# PoE.net
KiCad netlist of a schematic drawn in Altium Designer
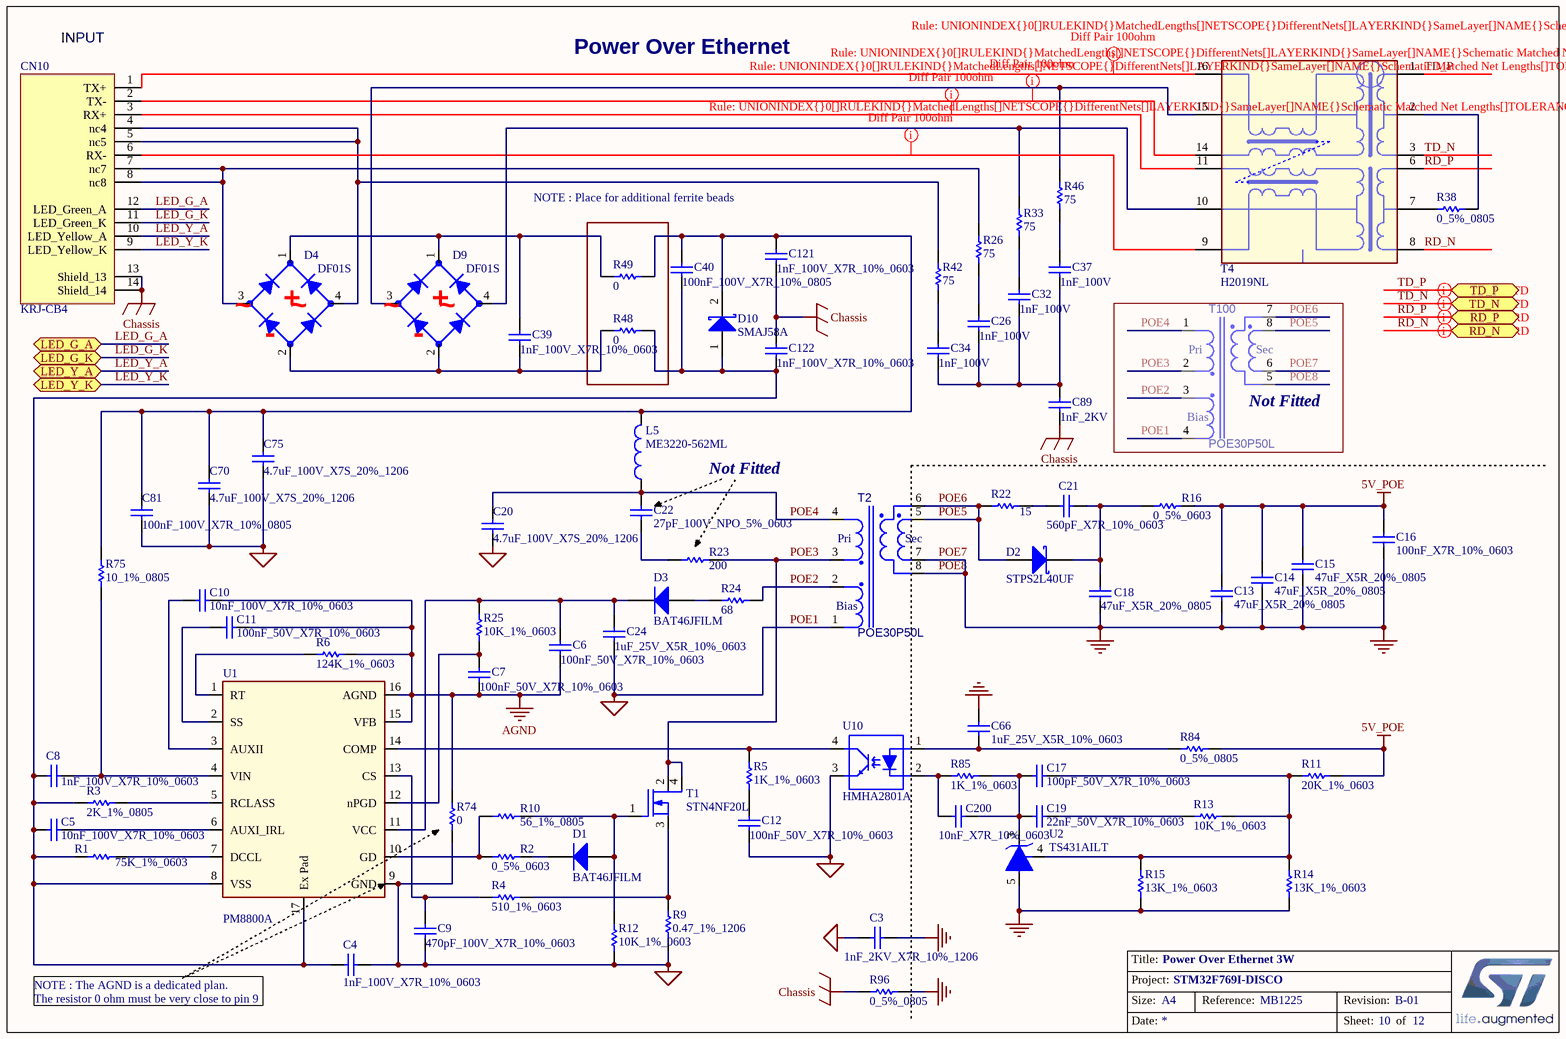
[diagram p0: PoE.SchDoc]

(export (version "E")
  (design (tool "Eeschema 10.0.6"))
  (components
    (comp (ref "C3")
      (value "1nF_2KV_X7R_10%_1206")
      (footprint "1206C")
      (description "Capacitor,1nF,2KV,X7R,10%,1206,YAGEO")
      (libsource (lib "MCD_TOOLS_CAPACITOR") (part "Cap_1nF_2KV_X7R_10%_1206"))
    )
    (comp (ref "C4")
      (value "1nF_100V_X7R_10%_0603")
      (footprint "0603C")
      (description "Capacitor,1nF,100V,X7R,10%,0603,YAGEO")
      (libsource (lib "MCD_TOOLS_CAPACITOR") (part "Cap_1nF_100V_X7R_10%_0603"))
    )
    (comp (ref "C5")
      (value "10nF_100V_X7R_10%_0603")
      (footprint "0603C")
      (description "Capacitor,10nF,100V,X7R,10%,0603,YAGEO")
      (libsource (lib "MCD_TOOLS_CAPACITOR") (part "Cap_10nF_100V_X7R_10%_0603"))
    )
    (comp (ref "C6")
      (value "100nF_50V_X7R_10%_0603")
      (footprint "0603C")
      (description "Capacitor,100nF,50V,X7R,10%,0603,YAGEO")
      (libsource (lib "MCD_TOOLS_CAPACITOR") (part "Cap_100nF_50V_X7R_10%_0603"))
    )
    (comp (ref "C7")
      (value "100nF_50V_X7R_10%_0603")
      (footprint "0603C")
      (description "Capacitor,100nF,50V,X7R,10%,0603,YAGEO")
      (libsource (lib "MCD_TOOLS_CAPACITOR") (part "Cap_100nF_50V_X7R_10%_0603"))
    )
    (comp (ref "C8")
      (value "1nF_100V_X7R_10%_0603")
      (footprint "0603C")
      (description "Capacitor,1nF,100V,X7R,10%,0603,YAGEO")
      (libsource (lib "MCD_TOOLS_CAPACITOR") (part "Cap_1nF_100V_X7R_10%_0603"))
    )
    (comp (ref "C9")
      (value "470pF_100V_X7R_10%_0603")
      (footprint "0603C")
      (description "Capacitor,470pF,100V,X7R,10%,0603,AVX")
      (libsource (lib "MCD_TOOLS_CAPACITOR") (part "Cap_470pF_100V_X7R_10%_0603"))
    )
    (comp (ref "C10")
      (value "10nF_100V_X7R_10%_0603")
      (footprint "0603C")
      (description "Capacitor,10nF,100V,X7R,10%,0603,YAGEO")
      (libsource (lib "MCD_TOOLS_CAPACITOR") (part "Cap_10nF_100V_X7R_10%_0603"))
    )
    (comp (ref "C11")
      (value "100nF_50V_X7R_10%_0603")
      (footprint "0603C")
      (description "Capacitor,100nF,50V,X7R,10%,0603,YAGEO")
      (libsource (lib "MCD_TOOLS_CAPACITOR") (part "Cap_100nF_50V_X7R_10%_0603"))
    )
    (comp (ref "C12")
      (value "100nF_50V_X7R_10%_0603")
      (footprint "0603C")
      (description "Capacitor,100nF,50V,X7R,10%,0603,YAGEO")
      (libsource (lib "MCD_TOOLS_CAPACITOR") (part "Cap_100nF_50V_X7R_10%_0603"))
    )
    (comp (ref "C13")
      (value "47uF_X5R_20%_0805")
      (footprint "0805C")
      (description "Capacitor,47uF,10V,X5R,20%,0805,MURATA")
      (libsource (lib "MCD_TOOLS_CAPACITOR") (part "Cap_47uF_X5R_20%_0805"))
    )
    (comp (ref "C14")
      (value "47uF_X5R_20%_0805")
      (footprint "0805C")
      (description "Capacitor,47uF,10V,X5R,20%,0805,MURATA")
      (libsource (lib "MCD_TOOLS_CAPACITOR") (part "Cap_47uF_X5R_20%_0805"))
    )
    (comp (ref "C15")
      (value "47uF_X5R_20%_0805")
      (footprint "0805C")
      (description "Capacitor,47uF,10V,X5R,20%,0805,MURATA")
      (libsource (lib "MCD_TOOLS_CAPACITOR") (part "Cap_47uF_X5R_20%_0805"))
    )
    (comp (ref "C16")
      (value "100nF_X7R_10%_0603")
      (footprint "0603C")
      (description "Capacitor,100nF,16V,X7R,10%,0603,YAGEO")
      (libsource (lib "MCD_TOOLS_CAPACITOR") (part "Cap_100nF_X7R_10%_0603"))
    )
    (comp (ref "C17")
      (value "100pF_50V_X7R_10%_0603")
      (footprint "0603C")
      (description "Capacitor,100pF,50V,X7R,10%,0603,AVX")
      (libsource (lib "MCD_TOOLS_CAPACITOR") (part "Cap_100pF_50V_X7R_10%_0603"))
    )
    (comp (ref "C18")
      (value "47uF_X5R_20%_0805")
      (footprint "0805C")
      (description "Capacitor,47uF,10V,X5R,20%,0805,MURATA")
      (libsource (lib "MCD_TOOLS_CAPACITOR") (part "Cap_47uF_X5R_20%_0805"))
    )
    (comp (ref "C19")
      (value "22nF_50V_X7R_10%_0603")
      (footprint "0603C")
      (description "Capacitor,22nF,50V,X7R,10%,0603,YAGEO")
      (libsource (lib "MCD_TOOLS_CAPACITOR") (part "Cap_22nF_50V_X7R_10%_0603"))
    )
    (comp (ref "C20")
      (value "4.7uF_100V_X7S_20%_1206")
      (footprint "1206C")
      (description "Capacitor,4.7uF,100V, X7S,20%,1206,AVX")
      (libsource (lib "MCD_TOOLS_CAPACITOR") (part "Cap_4.7uF_100V_X7S_20%_1206"))
    )
    (comp (ref "C21")
      (value "560pF_X7R_10%_0603")
      (footprint "0603C")
      (description "Capacitor,560pF,16V,X7R,10%,0603,AVX")
      (libsource (lib "MCD_TOOLS_CAPACITOR") (part "Cap_560pF_X7R_10%_0603"))
    )
    (comp (ref "C22")
      (value "27pF_100V_NPO_5%_0603")
      (footprint "0603C")
      (description "Capacitor,27pF,100V,NPO,5%,0603,YAGEO")
      (libsource (lib "MCD_TOOLS_CAPACITOR") (part "Cap_27pF_100V_NPO_5%_0603"))
    )
    (comp (ref "C24")
      (value "1uF_25V_X5R_10%_0603")
      (footprint "0603C")
      (description "Capacitor,1uF,25V,X5R,10%,0603,YAGEO")
      (libsource (lib "MCD_TOOLS_CAPACITOR") (part "Cap_1uF_25V_X5R_10%_0603"))
    )
    (comp (ref "C26")
      (value "1nF_100V")
      (footprint "0603C")
      (description "Capacitor,1nF,100V,X7R,10%,0603,YAGEO")
      (libsource (lib "MCD_TOOLS_CAPACITOR") (part "Cap_1nF_100V_X7R_10%_0603"))
    )
    (comp (ref "C32")
      (value "1nF_100V")
      (footprint "0603C")
      (description "Capacitor,1nF,100V,X7R,10%,0603,YAGEO")
      (libsource (lib "MCD_TOOLS_CAPACITOR") (part "Cap_1nF_100V_X7R_10%_0603"))
    )
    (comp (ref "C34")
      (value "1nF_100V")
      (footprint "0603C")
      (description "Capacitor,1nF,100V,X7R,10%,0603,YAGEO")
      (libsource (lib "MCD_TOOLS_CAPACITOR") (part "Cap_1nF_100V_X7R_10%_0603"))
    )
    (comp (ref "C37")
      (value "1nF_100V")
      (footprint "0603C")
      (description "Capacitor,1nF,100V,X7R,10%,0603,YAGEO")
      (libsource (lib "MCD_TOOLS_CAPACITOR") (part "Cap_1nF_100V_X7R_10%_0603"))
    )
    (comp (ref "C39")
      (value "1nF_100V_X7R_10%_0603")
      (footprint "0603C")
      (description "Capacitor,1nF,100V,X7R,10%,0603,YAGEO")
      (libsource (lib "MCD_TOOLS_CAPACITOR") (part "Cap_1nF_100V_X7R_10%_0603"))
    )
    (comp (ref "C40")
      (value "100nF_100V_X7R_10%_0805")
      (footprint "0805C")
      (description "Capacitor,100nF,100V,X7R,10%,0805,TDK")
      (libsource (lib "MCD_TOOLS_CAPACITOR") (part "Cap_100nF_100V_X7R_10%_0805"))
    )
    (comp (ref "C66")
      (value "1uF_25V_X5R_10%_0603")
      (footprint "0603C")
      (description "Capacitor,1uF,25V,X5R,10%,0603,YAGEO")
      (libsource (lib "MCD_TOOLS_CAPACITOR") (part "Cap_1uF_25V_X5R_10%_0603"))
    )
    (comp (ref "C70")
      (value "4.7uF_100V_X7S_20%_1206")
      (footprint "1206C")
      (description "Capacitor,4.7uF,100V, X7S,20%,1206,AVX")
      (libsource (lib "MCD_TOOLS_CAPACITOR") (part "Cap_4.7uF_100V_X7S_20%_1206"))
    )
    (comp (ref "C75")
      (value "4.7uF_100V_X7S_20%_1206")
      (footprint "1206C")
      (description "Capacitor,4.7uF,100V, X7S,20%,1206,AVX")
      (libsource (lib "MCD_TOOLS_CAPACITOR") (part "Cap_4.7uF_100V_X7S_20%_1206"))
    )
    (comp (ref "C81")
      (value "100nF_100V_X7R_10%_0805")
      (footprint "0805C")
      (description "Capacitor,100nF,100V,X7R,10%,0805,TDK")
      (libsource (lib "MCD_TOOLS_CAPACITOR") (part "Cap_100nF_100V_X7R_10%_0805"))
    )
    (comp (ref "C89")
      (value "1nF_2KV")
      (footprint "1206C")
      (description "Capacitor,1nF,2KV,X7R,10%,1206,YAGEO")
      (libsource (lib "MCD_TOOLS_CAPACITOR") (part "Cap_1nF_2KV_X7R_10%_1206"))
    )
    (comp (ref "C121")
      (value "1nF_100V_X7R_10%_0603")
      (footprint "0603C")
      (description "Capacitor,1nF,100V,X7R,10%,0603,YAGEO")
      (libsource (lib "MCD_TOOLS_CAPACITOR") (part "Cap_1nF_100V_X7R_10%_0603"))
    )
    (comp (ref "C122")
      (value "1nF_100V_X7R_10%_0603")
      (footprint "0603C")
      (description "Capacitor,1nF,100V,X7R,10%,0603,YAGEO")
      (libsource (lib "MCD_TOOLS_CAPACITOR") (part "Cap_1nF_100V_X7R_10%_0603"))
    )
    (comp (ref "C200")
      (value "10nF_X7R_10%_0603")
      (footprint "0603C")
      (description "Capacitor,10nF,50V,X7R,10%,0603,YAGEO")
      (libsource (lib "MCD_TOOLS_CAPACITOR") (part "Cap_10nF_X7R_10%_0603"))
    )
    (comp (ref "CN10")
      (value "KRJ-CB4")
      (footprint "RJ45_LED_KRJ-CB4R2GYZNL_EM")
      (description "100 Base-TX (Fast Ethernet)  RJ45 single port (1x1) with LEDS Integrated Connector")
      (libsource (lib "MCD_TOOLS_CONNECTOR") (part "KRJ-CB4"))
    )
    (comp (ref "D1")
      (value "BAT46JFILM")
      (footprint "SOD-323")
      (description "Schottky Single diode(150mA, 100V)")
      (libsource (lib "MCD_TOOLS_MISCELLANEOUS") (part "BAT46JFILM"))
    )
    (comp (ref "D2")
      (value "STPS2L40UF")
      (footprint "SMB")
      (description "Low drop power Schottky rectifier(2A, 40V, 0.34V)")
      (libsource (lib "MCD_TOOLS_MISCELLANEOUS") (part "STPS2L40UF"))
    )
    (comp (ref "D3")
      (value "BAT46JFILM")
      (footprint "SOD-323")
      (description "Schottky Single diode(150mA, 100V)")
      (libsource (lib "MCD_TOOLS_MISCELLANEOUS") (part "BAT46JFILM"))
    )
    (comp (ref "D4")
      (value "DF01S")
      (footprint "DBS101-107G")
      (description "Surface Mount Bridge Rectifiers")
      (libsource (lib "MCD_TOOLS_MISCELLANEOUS") (part "DF01S_SMD"))
    )
    (comp (ref "D9")
      (value "DF01S")
      (footprint "DBS101-107G")
      (description "Surface Mount Bridge Rectifiers")
      (libsource (lib "MCD_TOOLS_MISCELLANEOUS") (part "DF01S_SMD"))
    )
    (comp (ref "D10")
      (value "SMAJ58A")
      (footprint "SMA")
      (description "Transil 400W, VRM=58V")
      (libsource (lib "MCD_TOOLS_MISCELLANEOUS") (part "SMAJ58A"))
    )
    (comp (ref "L5")
      (value "ME3220-562ML")
      (footprint "LSM2_3R2X2R8_H2")
      (description "Power Inductor, 5.6uH, 0.2R, ME3220-562ML, CoilCraft")
      (libsource (lib "MCD_TOOLS_MISCELLANEOUS") (part "ME3220-562ML"))
    )
    (comp (ref "R1")
      (value "75K_1%_0603")
      (footprint "0603R")
      (description "Resistor,75K,0603,1%,YAGEO")
      (libsource (lib "MCD_TOOLS_RESISTOR") (part "Res_75K_1%_0603"))
    )
    (comp (ref "R2")
      (value "0_5%_0603")
      (footprint "0603R-GS")
      (description "Resistor,0,0603,5%,YAGEO")
      (libsource (lib "MCD_TOOLS_RESISTOR") (part "Res_0_5%_0603"))
    )
    (comp (ref "R3")
      (value "2K_1%_0805")
      (footprint "0805R")
      (description "Resistor,2K,0805,1%,YAGEO")
      (libsource (lib "MCD_TOOLS_RESISTOR") (part "Res_2K_1%_0805"))
    )
    (comp (ref "R4")
      (value "510_1%_0603")
      (footprint "0603R")
      (description "Resistor,510,0603,1%,YAGEO")
      (libsource (lib "MCD_TOOLS_RESISTOR") (part "Res_510_1%_0603"))
    )
    (comp (ref "R5")
      (value "1K_1%_0603")
      (footprint "0603R")
      (description "Resistor,1K,0603,1%,YAGEO")
      (libsource (lib "MCD_TOOLS_RESISTOR") (part "Res_1K_1%_0603"))
    )
    (comp (ref "R6")
      (value "124K_1%_0603")
      (footprint "0603R")
      (description "Resistor,124K,0603,1%,YAGEO")
      (libsource (lib "MCD_TOOLS_RESISTOR") (part "Res_124K_1%_0603"))
    )
    (comp (ref "R9")
      (value "0.47_1%_1206")
      (footprint "1206R")
      (description "Resistor,0.47,1206,1%,YAGEO")
      (libsource (lib "MCD_TOOLS_RESISTOR") (part "Res_0.47_1%_1206"))
    )
    (comp (ref "R10")
      (value "56_1%_0805")
      (footprint "0805R")
      (description "Resistor,56,0805,1%,YAGEO")
      (libsource (lib "MCD_TOOLS_RESISTOR") (part "Res_56_1%_0805"))
    )
    (comp (ref "R11")
      (value "20K_1%_0603")
      (footprint "0603R")
      (description "Resistor,20K,0603,1%,YAGEO")
      (libsource (lib "MCD_TOOLS_RESISTOR") (part "Res_20K_1%_0603"))
    )
    (comp (ref "R12")
      (value "10K_1%_0603")
      (footprint "0603R")
      (description "Resistor,10K,0603,1%,YAGEO")
      (libsource (lib "MCD_TOOLS_RESISTOR") (part "Res_10K_1%_0603"))
    )
    (comp (ref "R13")
      (value "10K_1%_0603")
      (footprint "0603R")
      (description "Resistor,10K,0603,1%,YAGEO")
      (libsource (lib "MCD_TOOLS_RESISTOR") (part "Res_10K_1%_0603"))
    )
    (comp (ref "R14")
      (value "13K_1%_0603")
      (footprint "0603R")
      (description "Resistor,13K,0603,1%,YAGEO")
      (libsource (lib "MCD_TOOLS_RESISTOR") (part "Res_13K_1%_0603"))
    )
    (comp (ref "R15")
      (value "13K_1%_0603")
      (footprint "0603R")
      (description "Resistor,13K,0603,1%,YAGEO")
      (libsource (lib "MCD_TOOLS_RESISTOR") (part "Res_13K_1%_0603"))
    )
    (comp (ref "R16")
      (value "0_5%_0603")
      (footprint "0603R-GS")
      (description "Resistor,0,0603,5%,YAGEO")
      (libsource (lib "MCD_TOOLS_RESISTOR") (part "Res_0_5%_0603"))
    )
    (comp (ref "R22")
      (value "15")
      (footprint "0805R")
      (description "Resistor,15,0805,1%,YAGEO")
      (libsource (lib "MCD_TOOLS_RESISTOR") (part "Res_15_1%_0805"))
    )
    (comp (ref "R23")
      (value "200")
      (footprint "1206R")
      (description "Resistor,200,1206,1%,Rohm")
      (libsource (lib "MCD_TOOLS_RESISTOR") (part "Res_200_1%_1206"))
    )
    (comp (ref "R24")
      (value "68")
      (footprint "0805R")
      (description "Resistor,68,0805,1%,YAGEO")
      (libsource (lib "MCD_TOOLS_RESISTOR") (part "Res_68_1%_0805"))
    )
    (comp (ref "R25")
      (value "10K_1%_0603")
      (footprint "0603R")
      (description "Resistor,10K,0603,1%,YAGEO")
      (libsource (lib "MCD_TOOLS_RESISTOR") (part "Res_10K_1%_0603"))
    )
    (comp (ref "R26")
      (value "75")
      (footprint "0805R")
      (description "Resistor,75,0805,1%,YAGEO")
      (libsource (lib "MCD_TOOLS_RESISTOR") (part "Res_75_1%_0805"))
    )
    (comp (ref "R33")
      (value "75")
      (footprint "0805R")
      (description "Resistor,75,0805,1%,YAGEO")
      (libsource (lib "MCD_TOOLS_RESISTOR") (part "Res_75_1%_0805"))
    )
    (comp (ref "R38")
      (value "0_5%_0805")
      (footprint "0805R")
      (description "Resistor,0,0805,5%,YAGEO")
      (libsource (lib "MCD_TOOLS_RESISTOR") (part "Res_0_5%_0805"))
    )
    (comp (ref "R42")
      (value "75")
      (footprint "0805R")
      (description "Resistor,75,0805,1%,YAGEO")
      (libsource (lib "MCD_TOOLS_RESISTOR") (part "Res_75_1%_0805"))
    )
    (comp (ref "R46")
      (value "75")
      (footprint "0805R")
      (description "Resistor,75,0805,1%,YAGEO")
      (libsource (lib "MCD_TOOLS_RESISTOR") (part "Res_75_1%_0805"))
    )
    (comp (ref "R48")
      (value "0")
      (footprint "0805R")
      (description "Resistor,0,0805,5%,YAGEO")
      (libsource (lib "MCD_TOOLS_RESISTOR") (part "Res_0_5%_0805"))
    )
    (comp (ref "R49")
      (value "0")
      (footprint "0805R")
      (description "Resistor,0,0805,5%,YAGEO")
      (libsource (lib "MCD_TOOLS_RESISTOR") (part "Res_0_5%_0805"))
    )
    (comp (ref "R74")
      (value "0")
      (footprint "0603R-GS")
      (description "Resistor,0,0603,5%,YAGEO")
      (libsource (lib "MCD_TOOLS_RESISTOR") (part "Res_0_5%_0603"))
    )
    (comp (ref "R75")
      (value "10_1%_0805")
      (footprint "0805R")
      (description "Resistor,10,0805,1%,Stackpole,1/4W")
      (libsource (lib "MCD_TOOLS_RESISTOR") (part "Res_10_1%_0805"))
    )
    (comp (ref "R84")
      (value "0_5%_0805")
      (footprint "0805R")
      (description "Resistor,0,0805,5%,YAGEO")
      (libsource (lib "MCD_TOOLS_RESISTOR") (part "Res_0_5%_0805"))
    )
    (comp (ref "R85")
      (value "1K_1%_0603")
      (footprint "0603R")
      (description "Resistor,1K,0603,1%,YAGEO")
      (libsource (lib "MCD_TOOLS_RESISTOR") (part "Res_1K_1%_0603"))
    )
    (comp (ref "R96")
      (value "0_5%_0805")
      (footprint "0805R")
      (description "Resistor,0,0805,5%,YAGEO")
      (libsource (lib "MCD_TOOLS_RESISTOR") (part "Res_0_5%_0805"))
    )
    (comp (ref "T1")
      (value "STN4NF20L")
      (footprint "SOT-223")
      (description "N-channel 200 V, 1.1ohm, 1 A, low gate charge STripFET II, Power MOSFET")
      (libsource (lib "MCD_TOOLS_MISCELLANEOUS") (part "STN4NF20L"))
    )
    (comp (ref "T2")
      (value "POE30P50L")
      (footprint "TF_10R9X13R2-12R2X14R4_CPT")
      (description "Flyback Transformers for 3 Watt, PoE applications, CoilCraft Cyntec")
      (fields (field (name "PROVIDED") "Sub Co"))
      (libsource (lib "MCD_TOOLS_MISCELLANEOUS") (part "POE30P_C"))
    )
    (comp (ref "T4")
      (value "H2019NL")
      (footprint "TF_16SM_12R7X9R65")
      (description "10/100BASE-TX VoIP Magnetics Modules, Data Transformer")
      (libsource (lib "MCD_TOOLS_MISCELLANEOUS") (part "H2019"))
    )
    (comp (ref "T100")
      (value "POE30P50L")
      (footprint "TF_8SM_12R04X12R85")
      (description "Flyback Transformers for 3 Watt, PoE applications, Wurth")
      (fields (field (name "PROVIDED") "Sub Co"))
      (libsource (lib "MCD_TOOLS_MISCELLANEOUS") (part "POE30P_W"))
    )
    (comp (ref "U1")
      (value "PM8800A")
      (footprint "TSSOP16_0R65_5x6R4_TP")
      (fields (field (name "PROVIDED") "STM"))
      (libsource (lib "MCD_TOOLS_MISCELLANEOUS") (part "PM8800A"))
    )
    (comp (ref "U2")
      (value "TS431AILT")
      (footprint "SOT23-5")
      (description "Low voltage adjustable shunt reference")
      (libsource (lib "MCD_TOOLS_MISCELLANEOUS") (part "TS431AILT"))
    )
    (comp (ref "U10")
      (value "HMHA2801A")
      (footprint "PC_4SM_1R27_2R5X6R8")
      (description "OPTOISOLATOR 3.7KV TRANSISTOR 4SMD")
      (libsource (lib "MCD_TOOLS_MISCELLANEOUS") (part "HMHA2801A"))
    )
  )
  (nets
    (net (code "1") (name "/LED_G_A") (class "Default")
      (node (ref "CN10") (pin "12") (pinfunction "LED_Green_A_12") (pintype "passive"))
    )
    (net (code "2") (name "/LED_G_K") (class "Default")
      (node (ref "CN10") (pin "11") (pinfunction "LED_Green_K_11") (pintype "passive"))
    )
    (net (code "3") (name "/LED_Y_A") (class "Default")
      (node (ref "CN10") (pin "10") (pinfunction "LED_Yellow_A_10") (pintype "passive"))
    )
    (net (code "4") (name "/LED_Y_K") (class "Default")
      (node (ref "CN10") (pin "9") (pinfunction "LED_Yellow_K_9") (pintype "passive"))
    )
    (net (code "5") (name "/POE2") (class "Default")
      (node (ref "R24") (pin "2") (pinfunction "2_2") (pintype "passive"))
      (node (ref "T100") (pin "3") (pinfunction "3_3") (pintype "passive"))
      (node (ref "T2") (pin "2") (pinfunction "2_2") (pintype "passive"))
    )
    (net (code "6") (name "/POE3") (class "Default")
      (node (ref "R23") (pin "2") (pinfunction "2_2") (pintype "passive"))
      (node (ref "T1") (pin "2") (pinfunction "D_2") (pintype "passive"))
      (node (ref "T1") (pin "4") (pinfunction "D_4") (pintype "passive"))
      (node (ref "T100") (pin "2") (pinfunction "2_2") (pintype "passive"))
      (node (ref "T2") (pin "3") (pinfunction "3_3") (pintype "passive"))
    )
    (net (code "7") (name "/POE4") (class "Default")
      (node (ref "C20") (pin "2") (pinfunction "2_2") (pintype "passive"))
      (node (ref "C22") (pin "2") (pinfunction "2_2") (pintype "passive"))
      (node (ref "L5") (pin "1") (pinfunction "1_1") (pintype "passive"))
      (node (ref "T100") (pin "1") (pinfunction "1_1") (pintype "passive"))
      (node (ref "T2") (pin "4") (pinfunction "4_4") (pintype "passive"))
    )
    (net (code "8") (name "/POE5") (class "Default")
      (node (ref "D2") (pin "1") (pinfunction "A_1") (pintype "passive"))
      (node (ref "R22") (pin "1") (pinfunction "1_1") (pintype "passive"))
      (node (ref "T100") (pin "7") (pinfunction "7_7") (pintype "passive"))
      (node (ref "T100") (pin "8") (pinfunction "8_8") (pintype "passive"))
      (node (ref "T2") (pin "5") (pinfunction "5_5") (pintype "passive"))
      (node (ref "T2") (pin "6") (pinfunction "6_6") (pintype "passive"))
    )
    (net (code "9") (name "/RD_N") (class "Default")
      (node (ref "T4") (pin "8") (pinfunction "rd-_8") (pintype "passive"))
    )
    (net (code "10") (name "/RD_P") (class "Default")
      (node (ref "T4") (pin "6") (pinfunction "rd+_6") (pintype "passive"))
    )
    (net (code "11") (name "/TD_N") (class "Default")
      (node (ref "T4") (pin "3") (pinfunction "td-_3") (pintype "passive"))
    )
    (net (code "12") (name "/TD_P") (class "Default")
      (node (ref "T4") (pin "1") (pinfunction "td+_1") (pintype "passive"))
    )
    (net (code "13") (name "5V_POE") (class "Default")
      (node (ref "C13") (pin "2") (pinfunction "2_2") (pintype "passive"))
      (node (ref "C14") (pin "2") (pinfunction "2_2") (pintype "passive"))
      (node (ref "C15") (pin "2") (pinfunction "2_2") (pintype "passive"))
      (node (ref "C16") (pin "2") (pinfunction "2_2") (pintype "passive"))
      (node (ref "R11") (pin "2") (pinfunction "2_2") (pintype "passive"))
      (node (ref "R16") (pin "2") (pinfunction "2_2") (pintype "passive"))
      (node (ref "R84") (pin "2") (pinfunction "2_2") (pintype "passive"))
    )
    (net (code "14") (name "AGND") (class "Default")
      (node (ref "C10") (pin "2") (pinfunction "2_2") (pintype "passive"))
      (node (ref "C11") (pin "2") (pinfunction "2_2") (pintype "passive"))
      (node (ref "C6") (pin "1") (pinfunction "1_1") (pintype "passive"))
      (node (ref "C7") (pin "1") (pinfunction "1_1") (pintype "passive"))
      (node (ref "R6") (pin "2") (pinfunction "2_2") (pintype "passive"))
      (node (ref "R74") (pin "2") (pinfunction "2_2") (pintype "passive"))
      (node (ref "U1") (pin "15") (pinfunction "VFB_15") (pintype "passive"))
      (node (ref "U1") (pin "16") (pinfunction "AGND_16") (pintype "passive"))
    )
    (net (code "15") (name "Chassis") (class "Default")
      (node (ref "C121") (pin "1") (pinfunction "1_1") (pintype "passive"))
      (node (ref "C122") (pin "2") (pinfunction "2_2") (pintype "passive"))
      (node (ref "C89") (pin "1") (pinfunction "1_1") (pintype "passive"))
      (node (ref "CN10") (pin "13") (pinfunction "Shield_13_13") (pintype "passive"))
      (node (ref "CN10") (pin "14") (pinfunction "Shield_14_14") (pintype "passive"))
      (node (ref "R96") (pin "1") (pinfunction "1_1") (pintype "passive"))
    )
    (net (code "16") (name "GND") (class "Default")
      (node (ref "C13") (pin "1") (pinfunction "1_1") (pintype "passive"))
      (node (ref "C14") (pin "1") (pinfunction "1_1") (pintype "passive"))
      (node (ref "C15") (pin "1") (pinfunction "1_1") (pintype "passive"))
      (node (ref "C16") (pin "1") (pinfunction "1_1") (pintype "passive"))
      (node (ref "C18") (pin "1") (pinfunction "1_1") (pintype "passive"))
      (node (ref "C3") (pin "2") (pinfunction "2_2") (pintype "passive"))
      (node (ref "C66") (pin "2") (pinfunction "2_2") (pintype "passive"))
      (node (ref "R14") (pin "1") (pinfunction "1_1") (pintype "passive"))
      (node (ref "R15") (pin "1") (pinfunction "1_1") (pintype "passive"))
      (node (ref "R96") (pin "2") (pinfunction "2_2") (pintype "passive"))
      (node (ref "T100") (pin "5") (pinfunction "5_5") (pintype "passive"))
      (node (ref "T100") (pin "6") (pinfunction "6_6") (pintype "passive"))
      (node (ref "T2") (pin "7") (pinfunction "7_7") (pintype "passive"))
      (node (ref "T2") (pin "8") (pinfunction "8_8") (pintype "passive"))
      (node (ref "U2") (pin "5") (pinfunction "A_5") (pintype "passive"))
    )
    (net (code "17") (name "GND_POWER_IN") (class "Default")
      (node (ref "C12") (pin "1") (pinfunction "1_1") (pintype "passive"))
      (node (ref "C20") (pin "1") (pinfunction "1_1") (pintype "passive"))
      (node (ref "C24") (pin "1") (pinfunction "1_1") (pintype "passive"))
      (node (ref "C3") (pin "1") (pinfunction "1_1") (pintype "passive"))
      (node (ref "C4") (pin "2") (pinfunction "2_2") (pintype "passive"))
      (node (ref "C70") (pin "1") (pinfunction "1_1") (pintype "passive"))
      (node (ref "C75") (pin "1") (pinfunction "1_1") (pintype "passive"))
      (node (ref "C81") (pin "1") (pinfunction "1_1") (pintype "passive"))
      (node (ref "C9") (pin "1") (pinfunction "1_1") (pintype "passive"))
      (node (ref "R12") (pin "1") (pinfunction "1_1") (pintype "passive"))
      (node (ref "R74") (pin "1") (pinfunction "1_1") (pintype "passive"))
      (node (ref "R9") (pin "1") (pinfunction "1_1") (pintype "passive"))
      (node (ref "T100") (pin "4") (pinfunction "4_4") (pintype "passive"))
      (node (ref "T2") (pin "1") (pinfunction "1_1") (pintype "passive"))
      (node (ref "U1") (pin "9") (pinfunction "GND_9") (pintype "passive"))
      (node (ref "U10") (pin "3") (pinfunction "Emitter_3") (pintype "passive"))
    )
    (net (code "18") (name "Net-(C12-Pad2)") (class "Default")
      (node (ref "C12") (pin "2") (pinfunction "2_2") (pintype "passive"))
      (node (ref "R5") (pin "1") (pinfunction "1_1") (pintype "passive"))
    )
    (net (code "19") (name "Net-(C19-Pad2)") (class "Default")
      (node (ref "C19") (pin "2") (pinfunction "2_2") (pintype "passive"))
      (node (ref "R13") (pin "1") (pinfunction "1_1") (pintype "passive"))
    )
    (net (code "20") (name "Net-(C21-Pad1)") (class "Default")
      (node (ref "C21") (pin "1") (pinfunction "1_1") (pintype "passive"))
      (node (ref "R22") (pin "2") (pinfunction "2_2") (pintype "passive"))
    )
    (net (code "21") (name "Net-(C22-Pad1)") (class "Default")
      (node (ref "C22") (pin "1") (pinfunction "1_1") (pintype "passive"))
      (node (ref "R23") (pin "1") (pinfunction "1_1") (pintype "passive"))
    )
    (net (code "22") (name "Net-(C26-Pad1)") (class "Default")
      (node (ref "C26") (pin "1") (pinfunction "1_1") (pintype "passive"))
      (node (ref "C32") (pin "1") (pinfunction "1_1") (pintype "passive"))
      (node (ref "C34") (pin "1") (pinfunction "1_1") (pintype "passive"))
      (node (ref "C37") (pin "1") (pinfunction "1_1") (pintype "passive"))
      (node (ref "C89") (pin "2") (pinfunction "2_2") (pintype "passive"))
    )
    (net (code "23") (name "Net-(C26-Pad2)") (class "Default")
      (node (ref "C26") (pin "2") (pinfunction "2_2") (pintype "passive"))
      (node (ref "R26") (pin "1") (pinfunction "1_1") (pintype "passive"))
    )
    (net (code "24") (name "Net-(C32-Pad2)") (class "Default")
      (node (ref "C32") (pin "2") (pinfunction "2_2") (pintype "passive"))
      (node (ref "R33") (pin "1") (pinfunction "1_1") (pintype "passive"))
    )
    (net (code "25") (name "Net-(C34-Pad2)") (class "Default")
      (node (ref "C34") (pin "2") (pinfunction "2_2") (pintype "passive"))
      (node (ref "R42") (pin "1") (pinfunction "1_1") (pintype "passive"))
    )
    (net (code "26") (name "Net-(C37-Pad2)") (class "Default")
      (node (ref "C37") (pin "2") (pinfunction "2_2") (pintype "passive"))
      (node (ref "R46") (pin "1") (pinfunction "1_1") (pintype "passive"))
    )
    (net (code "27") (name "Net-(CN10-RX+)") (class "Default")
      (node (ref "CN10") (pin "3") (pinfunction "RX+_3") (pintype "passive"))
      (node (ref "T4") (pin "11") (pinfunction "rx1+_11") (pintype "passive"))
    )
    (net (code "28") (name "Net-(CN10-RX-)") (class "Default")
      (node (ref "CN10") (pin "6") (pinfunction "RX-_6") (pintype "passive"))
      (node (ref "T4") (pin "9") (pinfunction "rx-_9") (pintype "passive"))
    )
    (net (code "29") (name "Net-(CN10-TX+)") (class "Default")
      (node (ref "CN10") (pin "1") (pinfunction "TX+_1") (pintype "passive"))
      (node (ref "T4") (pin "16") (pinfunction "tx1+_16") (pintype "passive"))
    )
    (net (code "30") (name "Net-(CN10-TX-)") (class "Default")
      (node (ref "CN10") (pin "2") (pinfunction "TX-_2") (pintype "passive"))
      (node (ref "T4") (pin "14") (pinfunction "tx1-_14") (pintype "passive"))
    )
    (net (code "31") (name "Net-(CN10-nc4)") (class "Default")
      (node (ref "CN10") (pin "4") (pinfunction "nc4_4") (pintype "passive"))
      (node (ref "CN10") (pin "5") (pinfunction "nc5_5") (pintype "passive"))
      (node (ref "D4") (pin "4") (pinfunction "AC_IN_1_4") (pintype "passive"))
      (node (ref "R42") (pin "2") (pinfunction "2_2") (pintype "passive"))
    )
    (net (code "32") (name "Net-(CN10-nc7)") (class "Default")
      (node (ref "CN10") (pin "7") (pinfunction "nc7_7") (pintype "passive"))
      (node (ref "CN10") (pin "8") (pinfunction "nc8_8") (pintype "passive"))
      (node (ref "D4") (pin "3") (pinfunction "AC_IN_2_3") (pintype "passive"))
      (node (ref "R26") (pin "2") (pinfunction "2_2") (pintype "passive"))
    )
    (net (code "33") (name "Net-(D1-A)") (class "Default")
      (node (ref "D1") (pin "1") (pinfunction "A_1") (pintype "passive"))
      (node (ref "R10") (pin "2") (pinfunction "2_2") (pintype "passive"))
      (node (ref "R12") (pin "2") (pinfunction "2_2") (pintype "passive"))
      (node (ref "T1") (pin "1") (pinfunction "G_1") (pintype "passive"))
    )
    (net (code "34") (name "Net-(D1-K)") (class "Default")
      (node (ref "D1") (pin "2") (pinfunction "K_2") (pintype "passive"))
      (node (ref "R2") (pin "2") (pinfunction "2_2") (pintype "passive"))
    )
    (net (code "35") (name "Net-(D2-K)") (class "Default")
      (node (ref "C18") (pin "2") (pinfunction "2_2") (pintype "passive"))
      (node (ref "C21") (pin "2") (pinfunction "2_2") (pintype "passive"))
      (node (ref "D2") (pin "2") (pinfunction "K_2") (pintype "passive"))
      (node (ref "R16") (pin "1") (pinfunction "1_1") (pintype "passive"))
    )
    (net (code "36") (name "Net-(D3-A)") (class "Default")
      (node (ref "D3") (pin "1") (pinfunction "A_1") (pintype "passive"))
      (node (ref "R24") (pin "1") (pinfunction "1_1") (pintype "passive"))
    )
    (net (code "37") (name "Net-(D3-K)") (class "Default")
      (node (ref "C24") (pin "2") (pinfunction "2_2") (pintype "passive"))
      (node (ref "C6") (pin "2") (pinfunction "2_2") (pintype "passive"))
      (node (ref "D3") (pin "2") (pinfunction "K_2") (pintype "passive"))
      (node (ref "R25") (pin "2") (pinfunction "2_2") (pintype "passive"))
      (node (ref "U1") (pin "11") (pinfunction "VCC_11") (pintype "passive"))
    )
    (net (code "38") (name "Net-(D4-DC_OUT_MINUS)") (class "Default")
      (node (ref "C39") (pin "1") (pinfunction "1_1") (pintype "passive"))
      (node (ref "D4") (pin "2") (pinfunction "DC_OUT_MINUS_2") (pintype "passive"))
      (node (ref "D9") (pin "2") (pinfunction "DC_OUT_MINUS_2") (pintype "passive"))
      (node (ref "R48") (pin "1") (pinfunction "1_1") (pintype "passive"))
    )
    (net (code "39") (name "Net-(D4-DC_OUT_PLUS)") (class "Default")
      (node (ref "C39") (pin "2") (pinfunction "2_2") (pintype "passive"))
      (node (ref "D4") (pin "1") (pinfunction "DC_OUT_PLUS_1") (pintype "passive"))
      (node (ref "D9") (pin "1") (pinfunction "DC_OUT_PLUS_1") (pintype "passive"))
      (node (ref "R49") (pin "1") (pinfunction "1_1") (pintype "passive"))
    )
    (net (code "40") (name "Net-(D9-AC_IN_1)") (class "Default")
      (node (ref "D9") (pin "4") (pinfunction "AC_IN_1_4") (pintype "passive"))
      (node (ref "R33") (pin "2") (pinfunction "2_2") (pintype "passive"))
      (node (ref "T4") (pin "10") (pinfunction "rxct_10") (pintype "passive"))
    )
    (net (code "41") (name "Net-(D9-AC_IN_2)") (class "Default")
      (node (ref "D9") (pin "3") (pinfunction "AC_IN_2_3") (pintype "passive"))
      (node (ref "R46") (pin "2") (pinfunction "2_2") (pintype "passive"))
      (node (ref "T4") (pin "15") (pinfunction "txct_15") (pintype "passive"))
    )
    (net (code "42") (name "Net-(D10-A)") (class "Default")
      (node (ref "C122") (pin "1") (pinfunction "1_1") (pintype "passive"))
      (node (ref "C4") (pin "1") (pinfunction "1_1") (pintype "passive"))
      (node (ref "C40") (pin "1") (pinfunction "1_1") (pintype "passive"))
      (node (ref "C5") (pin "1") (pinfunction "1_1") (pintype "passive"))
      (node (ref "C8") (pin "1") (pinfunction "1_1") (pintype "passive"))
      (node (ref "D10") (pin "1") (pinfunction "A_1") (pintype "passive"))
      (node (ref "R1") (pin "1") (pinfunction "1_1") (pintype "passive"))
      (node (ref "R3") (pin "1") (pinfunction "1_1") (pintype "passive"))
      (node (ref "R48") (pin "2") (pinfunction "2_2") (pintype "passive"))
      (node (ref "U1") (pin "17") (pinfunction "Ex_Pad_17") (pintype "passive"))
      (node (ref "U1") (pin "8") (pinfunction "VSS_8") (pintype "passive"))
    )
    (net (code "43") (name "Net-(D10-K)") (class "Default")
      (node (ref "C121") (pin "2") (pinfunction "2_2") (pintype "passive"))
      (node (ref "C40") (pin "2") (pinfunction "2_2") (pintype "passive"))
      (node (ref "C70") (pin "2") (pinfunction "2_2") (pintype "passive"))
      (node (ref "C75") (pin "2") (pinfunction "2_2") (pintype "passive"))
      (node (ref "C81") (pin "2") (pinfunction "2_2") (pintype "passive"))
      (node (ref "D10") (pin "2") (pinfunction "K_2") (pintype "passive"))
      (node (ref "L5") (pin "2") (pinfunction "2_2") (pintype "passive"))
      (node (ref "R49") (pin "2") (pinfunction "2_2") (pintype "passive"))
      (node (ref "R75") (pin "2") (pinfunction "2_2") (pintype "passive"))
    )
    (net (code "44") (name "Net-(T1-S)") (class "Default")
      (node (ref "R4") (pin "2") (pinfunction "2_2") (pintype "passive"))
      (node (ref "R9") (pin "2") (pinfunction "2_2") (pintype "passive"))
      (node (ref "T1") (pin "3") (pinfunction "S_3") (pintype "passive"))
    )
    (net (code "45") (name "Net-(T4-rct)") (class "Default")
      (node (ref "R38") (pin "1") (pinfunction "1_1") (pintype "passive"))
      (node (ref "T4") (pin "7") (pinfunction "rct_7") (pintype "passive"))
    )
    (net (code "46") (name "Net-(T4-tct)") (class "Default")
      (node (ref "R38") (pin "2") (pinfunction "2_2") (pintype "passive"))
      (node (ref "T4") (pin "2") (pinfunction "tct_2") (pintype "passive"))
    )
    (net (code "47") (name "Net-(U1-AUXII)") (class "Default")
      (node (ref "C10") (pin "1") (pinfunction "1_1") (pintype "passive"))
      (node (ref "U1") (pin "3") (pinfunction "AUXII_3") (pintype "passive"))
    )
    (net (code "48") (name "Net-(U1-AUXI_IRL)") (class "Default")
      (node (ref "C5") (pin "2") (pinfunction "2_2") (pintype "passive"))
      (node (ref "U1") (pin "6") (pinfunction "AUXI_IRL_6") (pintype "passive"))
    )
    (net (code "49") (name "Net-(U1-COMP)") (class "Default")
      (node (ref "R5") (pin "2") (pinfunction "2_2") (pintype "passive"))
      (node (ref "U1") (pin "14") (pinfunction "COMP_14") (pintype "passive"))
      (node (ref "U10") (pin "4") (pinfunction "Collector_4") (pintype "passive"))
    )
    (net (code "50") (name "Net-(U1-CS)") (class "Default")
      (node (ref "C9") (pin "2") (pinfunction "2_2") (pintype "passive"))
      (node (ref "R4") (pin "1") (pinfunction "1_1") (pintype "passive"))
      (node (ref "U1") (pin "13") (pinfunction "CS_13") (pintype "passive"))
    )
    (net (code "51") (name "Net-(U1-DCCL)") (class "Default")
      (node (ref "R1") (pin "2") (pinfunction "2_2") (pintype "passive"))
      (node (ref "U1") (pin "7") (pinfunction "DCCL_7") (pintype "passive"))
    )
    (net (code "52") (name "Net-(U1-GD)") (class "Default")
      (node (ref "R10") (pin "1") (pinfunction "1_1") (pintype "passive"))
      (node (ref "R2") (pin "1") (pinfunction "1_1") (pintype "passive"))
      (node (ref "U1") (pin "10") (pinfunction "GD_10") (pintype "passive"))
    )
    (net (code "53") (name "Net-(U1-RCLASS)") (class "Default")
      (node (ref "R3") (pin "2") (pinfunction "2_2") (pintype "passive"))
      (node (ref "U1") (pin "5") (pinfunction "RCLASS_5") (pintype "passive"))
    )
    (net (code "54") (name "Net-(U1-RT)") (class "Default")
      (node (ref "R6") (pin "1") (pinfunction "1_1") (pintype "passive"))
      (node (ref "U1") (pin "1") (pinfunction "RT_1") (pintype "passive"))
    )
    (net (code "55") (name "Net-(U1-SS)") (class "Default")
      (node (ref "C11") (pin "1") (pinfunction "1_1") (pintype "passive"))
      (node (ref "U1") (pin "2") (pinfunction "SS_2") (pintype "passive"))
    )
    (net (code "56") (name "Net-(U1-VIN)") (class "Default")
      (node (ref "C8") (pin "2") (pinfunction "2_2") (pintype "passive"))
      (node (ref "R75") (pin "1") (pinfunction "1_1") (pintype "passive"))
      (node (ref "U1") (pin "4") (pinfunction "VIN_4") (pintype "passive"))
    )
    (net (code "57") (name "Net-(U1-nPGD)") (class "Default")
      (node (ref "C7") (pin "2") (pinfunction "2_2") (pintype "passive"))
      (node (ref "R25") (pin "1") (pinfunction "1_1") (pintype "passive"))
      (node (ref "U1") (pin "12") (pinfunction "nPGD_12") (pintype "passive"))
    )
    (net (code "58") (name "Net-(U2-K)") (class "Default")
      (node (ref "C17") (pin "1") (pinfunction "1_1") (pintype "passive"))
      (node (ref "C19") (pin "1") (pinfunction "1_1") (pintype "passive"))
      (node (ref "C200") (pin "2") (pinfunction "2_2") (pintype "passive"))
      (node (ref "R85") (pin "2") (pinfunction "2_2") (pintype "passive"))
      (node (ref "U2") (pin "3") (pinfunction "K_3") (pintype "passive"))
    )
    (net (code "59") (name "Net-(U2-REF)") (class "Default")
      (node (ref "C17") (pin "2") (pinfunction "2_2") (pintype "passive"))
      (node (ref "R11") (pin "1") (pinfunction "1_1") (pintype "passive"))
      (node (ref "R13") (pin "2") (pinfunction "2_2") (pintype "passive"))
      (node (ref "R14") (pin "2") (pinfunction "2_2") (pintype "passive"))
      (node (ref "R15") (pin "2") (pinfunction "2_2") (pintype "passive"))
      (node (ref "U2") (pin "4") (pinfunction "REF_4") (pintype "passive"))
    )
    (net (code "60") (name "Net-(U10-Anode)") (class "Default")
      (node (ref "C66") (pin "1") (pinfunction "1_1") (pintype "passive"))
      (node (ref "R84") (pin "1") (pinfunction "1_1") (pintype "passive"))
      (node (ref "U10") (pin "1") (pinfunction "Anode_1") (pintype "passive"))
    )
    (net (code "61") (name "Net-(U10-B)") (class "Default")
      (node (ref "C200") (pin "1") (pinfunction "1_1") (pintype "passive"))
      (node (ref "R85") (pin "1") (pinfunction "1_1") (pintype "passive"))
      (node (ref "U10") (pin "2") (pinfunction "B_2") (pintype "passive"))
    )
    (net (code "62") (name "unconnected-(T4-nc_4-Pad4)") (class "Default")
      (node (ref "T4") (pin "4") (pinfunction "nc_4_4") (pintype "passive"))
    )
    (net (code "63") (name "unconnected-(T4-nc_5-Pad5)") (class "Default")
      (node (ref "T4") (pin "5") (pinfunction "nc_5_5") (pintype "passive"))
    )
    (net (code "64") (name "unconnected-(T4-nc_12-Pad12)") (class "Default")
      (node (ref "T4") (pin "12") (pinfunction "nc_12_12") (pintype "passive"))
    )
    (net (code "65") (name "unconnected-(T4-nc_13-Pad13)") (class "Default")
      (node (ref "T4") (pin "13") (pinfunction "nc_13_13") (pintype "passive"))
    )
    (net (code "66") (name "unconnected-(U2-nc_1-Pad1)") (class "Default")
      (node (ref "U2") (pin "1") (pinfunction "nc_1_1") (pintype "passive"))
    )
    (net (code "67") (name "unconnected-(U2-nc_2-Pad2)") (class "Default")
      (node (ref "U2") (pin "2") (pinfunction "nc_2_2") (pintype "passive"))
    )
  )
)
